# Power.net
KiCad netlist of a schematic drawn in Altium Designer
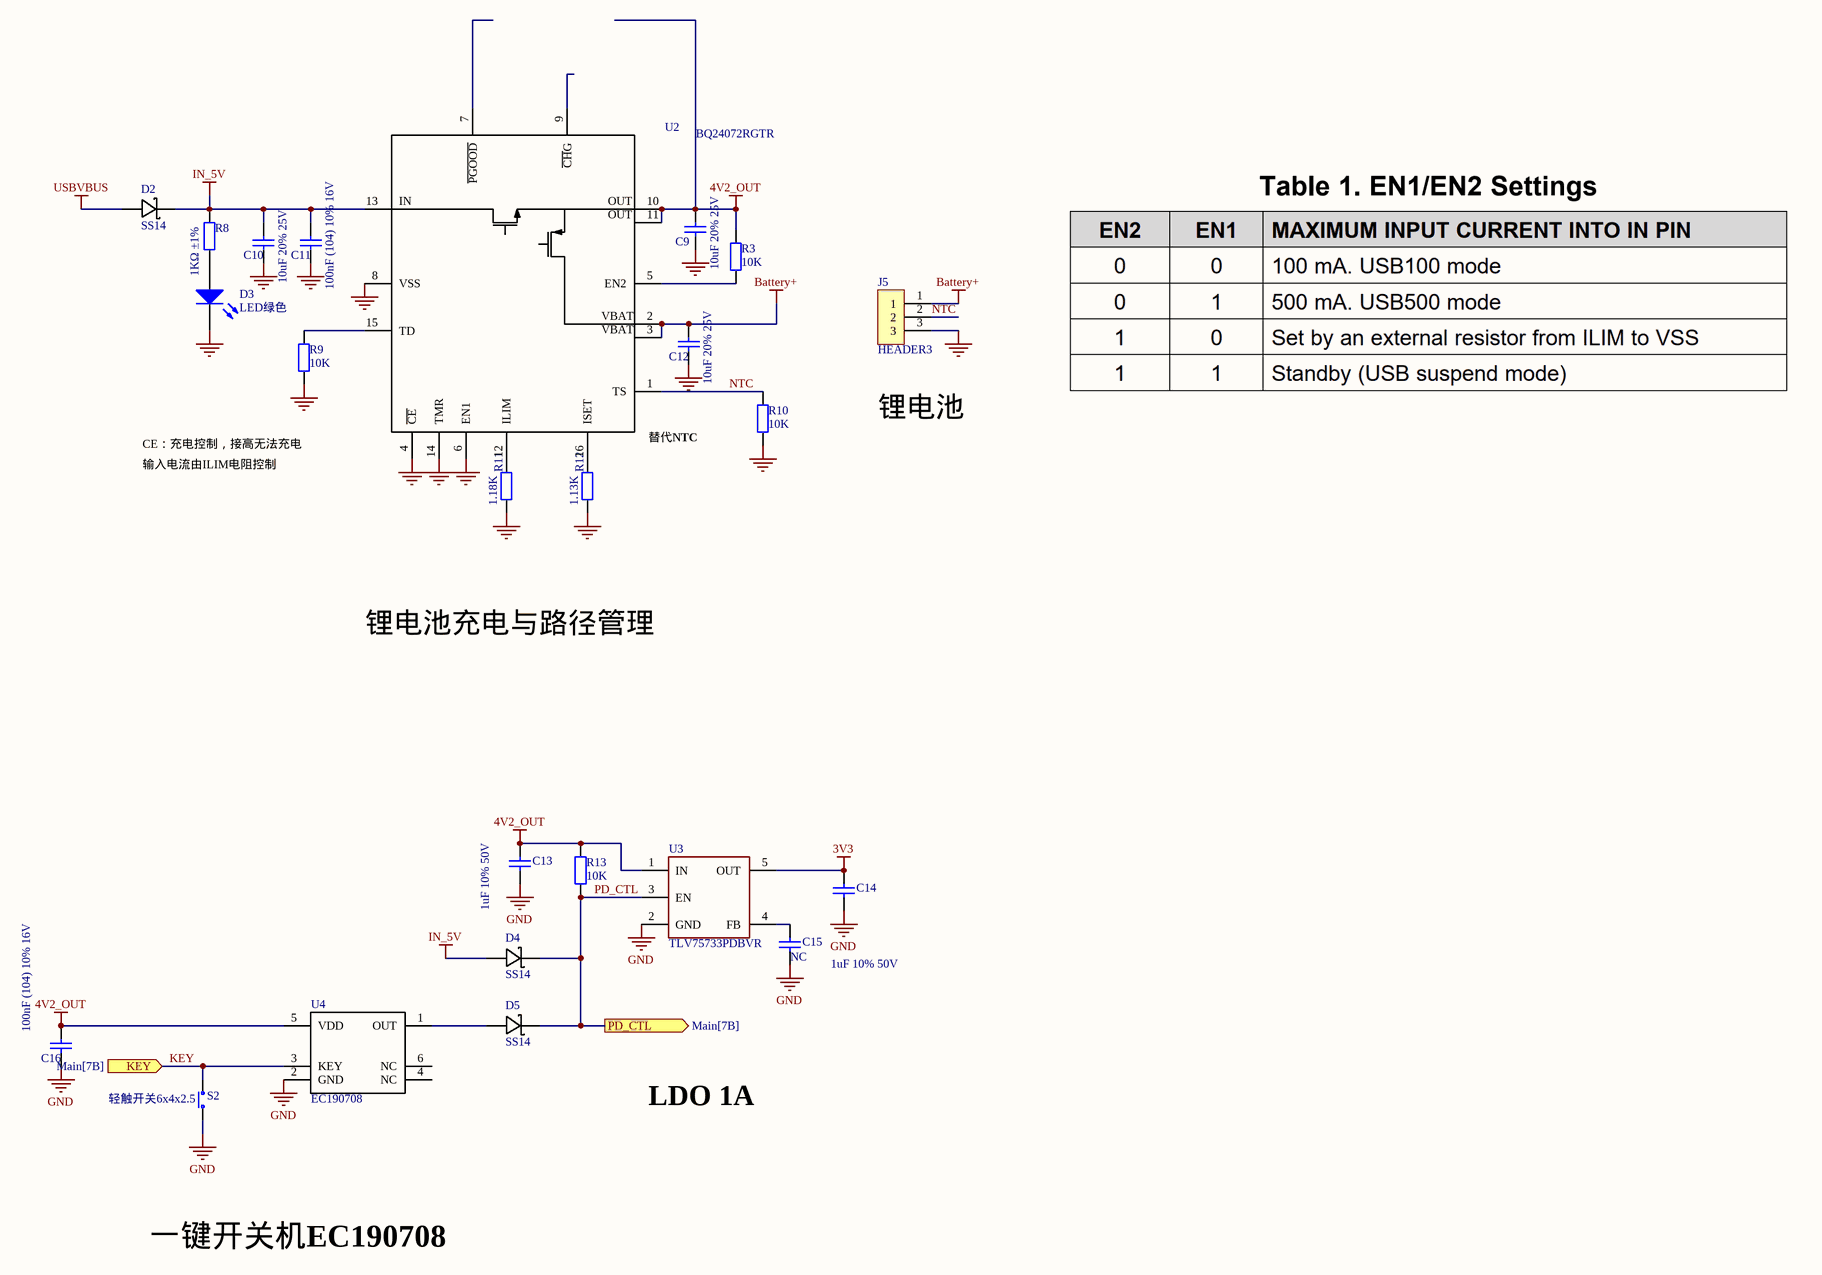
[diagram p0: Power.SchDoc]

(export (version "E")
  (design (tool "Eeschema 10.0.6"))
  (components
    (comp (ref "C9")
      (value "10uF 20% 25V")
      (footprint "0603_C")
      (description "贴片电容")
      (libsource (lib "Miscellaneous Devices LC") (part "0402 10uF (106) 20% 6.3V"))
    )
    (comp (ref "C10")
      (value "10uF 20% 25V")
      (footprint "0402_C")
      (description "贴片电容")
      (libsource (lib "Miscellaneous Devices LC") (part "0402 10uF (106) 20% 6.3V"))
    )
    (comp (ref "C11")
      (value "100nF (104) 10% 16V")
      (footprint "0402_C")
      (description "贴片电容")
      (libsource (lib "Miscellaneous Devices LC") (part "0603 100nF (104) 10% 50V"))
    )
    (comp (ref "C12")
      (value "10uF 20% 25V")
      (footprint "0603_C")
      (description "贴片电容")
      (libsource (lib "Miscellaneous Devices LC") (part "0402 10uF (106) 20% 6.3V"))
    )
    (comp (ref "C13")
      (value "1uF 10% 50V")
      (footprint "0402_C")
      (description "贴片电容")
      (libsource (lib "Cap") (part "0603 1uF (105) 10% 50V"))
    )
    (comp (ref "C14")
      (value "1uF 10% 50V")
      (footprint "0402_C")
      (description "贴片电容")
      (libsource (lib "Cap") (part "0603 1uF (105) 10% 50V"))
    )
    (comp (ref "C15")
      (value "NC")
      (footprint "0402_C")
      (description "贴片电容")
      (libsource (lib "Miscellaneous Devices LC") (part "0603 100nF (104) 10% 50V"))
    )
    (comp (ref "C16")
      (value "100nF (104) 10% 16V")
      (footprint "0402_C")
      (description "贴片电容")
      (libsource (lib "Miscellaneous Devices LC") (part "0603 100nF (104) 10% 50V"))
    )
    (comp (ref "D2")
      (value "SS14")
      (footprint "DO-214AC")
      (description "1A，40V")
      (libsource (lib "RFID") (part "SS14"))
    )
    (comp (ref "D3")
      (value "LED绿色")
      (footprint "LED_0402")
      (description "Typical INFRARED GaAs LED")
      (libsource (lib "RFID") (part "LED0"))
    )
    (comp (ref "D4")
      (value "SS14")
      (footprint "DO-214AC")
      (description "1A，40V")
      (libsource (lib "RFID") (part "SS14"))
    )
    (comp (ref "D5")
      (value "SS14")
      (footprint "DO-214AC")
      (description "1A，40V")
      (libsource (lib "RFID") (part "SS14"))
    )
    (comp (ref "J5") (value "HEADER3") (footprint "HEADER3") (libsource (lib "RFID") (part "HEADER3")))
    (comp (ref "R3")
      (value "10K")
      (footprint "0402_R")
      (description "Resistor")
      (libsource (lib "Miscellaneous Devices") (part "Res2"))
    )
    (comp (ref "R8")
      (value "1KΩ ±1%")
      (footprint "0402_R")
      (description "Resistor")
      (libsource (lib "") (part "Res2_1"))
    )
    (comp (ref "R9")
      (value "10K")
      (footprint "0402_R")
      (description "Resistor")
      (libsource (lib "Miscellaneous Devices") (part "Res2"))
    )
    (comp (ref "R10")
      (value "10K")
      (footprint "0402_R")
      (description "Resistor")
      (libsource (lib "Miscellaneous Devices") (part "Res2"))
    )
    (comp (ref "R11")
      (value "1.18K")
      (footprint "0402_R")
      (description "Resistor")
      (libsource (lib "Miscellaneous Devices") (part "Res2"))
    )
    (comp (ref "R12")
      (value "1.13K")
      (footprint "0402_R")
      (description "Resistor")
      (libsource (lib "Miscellaneous Devices") (part "Res2"))
    )
    (comp (ref "R13")
      (value "10K")
      (footprint "0402_R")
      (description "Resistor")
      (libsource (lib "") (part "Res2_1"))
    )
    (comp (ref "S2")
      (value "轻触开关6x4x2.5")
      (footprint "SW-SMD_L6.0-W4.0-LS7.2")
      (libsource (lib "RFID") (part "SW-PB_包脚U型小乌龟"))
    )
    (comp (ref "U2")
      (value "BQ24072RGTR")
      (footprint "QFN-16_L3.0-W3.0-P0.50-TL-EP")
      (description "TI")
      (libsource (lib "RFID") (part "BQ24072"))
    )
    (comp (ref "U3")
      (value "TLV75733PDBVR")
      (footprint "SOT-23_5")
      (libsource (lib "RFID") (part "TLV75733"))
    )
    (comp (ref "U4") (value "EC190708") (footprint "SOT-23-6") (libsource (lib "RFID") (part "EC190708")))
  )
  (nets
    (net (code "1") (name "/KEY") (class "Default")
      (node (ref "S2") (pin "1") (pinfunction "1_1") (pintype "passive"))
      (node (ref "U4") (pin "3") (pinfunction "KEY_3") (pintype "passive"))
    )
    (net (code "2") (name "/NTC") (class "Default")
      (node (ref "J5") (pin "2") (pinfunction "2_2") (pintype "power_in"))
      (node (ref "R10") (pin "1") (pinfunction "1_1") (pintype "passive"))
      (node (ref "U2") (pin "1") (pinfunction "TS_1") (pintype "passive"))
    )
    (net (code "3") (name "/PD_CTL") (class "Default")
      (node (ref "D4") (pin "2") (pinfunction "A_2") (pintype "passive"))
      (node (ref "D5") (pin "2") (pinfunction "A_2") (pintype "passive"))
      (node (ref "R13") (pin "1") (pinfunction "1_1") (pintype "passive"))
      (node (ref "U3") (pin "3") (pinfunction "EN_3") (pintype "passive"))
    )
    (net (code "4") (name "3V3") (class "Default")
      (node (ref "C14") (pin "2") (pinfunction "2_2") (pintype "passive"))
      (node (ref "U3") (pin "5") (pinfunction "OUT_5") (pintype "passive"))
    )
    (net (code "5") (name "4V2_OUT") (class "Default")
      (node (ref "C13") (pin "2") (pinfunction "2_2") (pintype "passive"))
      (node (ref "C16") (pin "2") (pinfunction "2_2") (pintype "passive"))
      (node (ref "C9") (pin "2") (pinfunction "2_2") (pintype "passive"))
      (node (ref "R13") (pin "2") (pinfunction "2_2") (pintype "passive"))
      (node (ref "R3") (pin "1") (pinfunction "1_1") (pintype "passive"))
      (node (ref "U2") (pin "10") (pinfunction "OUT_10") (pintype "passive"))
      (node (ref "U2") (pin "11") (pinfunction "OUT_11") (pintype "passive"))
      (node (ref "U3") (pin "1") (pinfunction "IN_1") (pintype "passive"))
      (node (ref "U4") (pin "5") (pinfunction "VDD_5") (pintype "passive"))
    )
    (net (code "6") (name "Battery+") (class "Default")
      (node (ref "C12") (pin "2") (pinfunction "2_2") (pintype "passive"))
      (node (ref "J5") (pin "1") (pinfunction "1_1") (pintype "power_in"))
      (node (ref "U2") (pin "2") (pinfunction "BAT_2") (pintype "passive"))
      (node (ref "U2") (pin "3") (pinfunction "BAT_3") (pintype "passive"))
    )
    (net (code "7") (name "GND") (class "Default")
      (node (ref "C10") (pin "1") (pinfunction "1_1") (pintype "passive"))
      (node (ref "C11") (pin "1") (pinfunction "1_1") (pintype "passive"))
      (node (ref "C12") (pin "1") (pinfunction "1_1") (pintype "passive"))
      (node (ref "C13") (pin "1") (pinfunction "1_1") (pintype "passive"))
      (node (ref "C14") (pin "1") (pinfunction "1_1") (pintype "passive"))
      (node (ref "C15") (pin "1") (pinfunction "1_1") (pintype "passive"))
      (node (ref "C16") (pin "1") (pinfunction "1_1") (pintype "passive"))
      (node (ref "C9") (pin "1") (pinfunction "1_1") (pintype "passive"))
      (node (ref "D3") (pin "K") (pinfunction "K_K") (pintype "passive"))
      (node (ref "J5") (pin "3") (pinfunction "3_3") (pintype "power_in"))
      (node (ref "R10") (pin "2") (pinfunction "2_2") (pintype "passive"))
      (node (ref "R11") (pin "2") (pinfunction "2_2") (pintype "passive"))
      (node (ref "R12") (pin "2") (pinfunction "2_2") (pintype "passive"))
      (node (ref "R9") (pin "2") (pinfunction "2_2") (pintype "passive"))
      (node (ref "S2") (pin "2") (pinfunction "2_2") (pintype "passive"))
      (node (ref "U2") (pin "14") (pinfunction "TMR_14") (pintype "passive"))
      (node (ref "U2") (pin "4") (pinfunction "~{CE}_4") (pintype "passive"))
      (node (ref "U2") (pin "6") (pinfunction "EN1_6") (pintype "passive"))
      (node (ref "U2") (pin "8") (pinfunction "VSS_8") (pintype "passive"))
      (node (ref "U3") (pin "2") (pinfunction "GND_2") (pintype "passive"))
      (node (ref "U4") (pin "2") (pinfunction "GND_2") (pintype "passive"))
    )
    (net (code "8") (name "IN_5V") (class "Default")
      (node (ref "C10") (pin "2") (pinfunction "2_2") (pintype "passive"))
      (node (ref "C11") (pin "2") (pinfunction "2_2") (pintype "passive"))
      (node (ref "D2") (pin "2") (pinfunction "A_2") (pintype "passive"))
      (node (ref "D4") (pin "1") (pinfunction "K_1") (pintype "passive"))
      (node (ref "R8") (pin "2") (pinfunction "2_2") (pintype "passive"))
      (node (ref "U2") (pin "13") (pinfunction "IN_13") (pintype "power_in"))
    )
    (net (code "9") (name "Net-(D3-PadA)") (class "Default")
      (node (ref "D3") (pin "A") (pinfunction "A_A") (pintype "passive"))
      (node (ref "R8") (pin "1") (pinfunction "1_1") (pintype "passive"))
    )
    (net (code "10") (name "Net-(D5-K)") (class "Default")
      (node (ref "D5") (pin "1") (pinfunction "K_1") (pintype "passive"))
      (node (ref "U4") (pin "1") (pinfunction "OUT_1") (pintype "passive"))
    )
    (net (code "11") (name "Net-(U2-EN2)") (class "Default")
      (node (ref "R3") (pin "2") (pinfunction "2_2") (pintype "passive"))
      (node (ref "U2") (pin "5") (pinfunction "EN2_5") (pintype "passive"))
    )
    (net (code "12") (name "Net-(U2-ILIM)") (class "Default")
      (node (ref "R11") (pin "1") (pinfunction "1_1") (pintype "passive"))
      (node (ref "U2") (pin "12") (pinfunction "ILIM_12") (pintype "passive"))
    )
    (net (code "13") (name "Net-(U2-ISET)") (class "Default")
      (node (ref "R12") (pin "1") (pinfunction "1_1") (pintype "passive"))
      (node (ref "U2") (pin "16") (pinfunction "ISET_16") (pintype "passive"))
    )
    (net (code "14") (name "Net-(U2-TD)") (class "Default")
      (node (ref "R9") (pin "1") (pinfunction "1_1") (pintype "passive"))
      (node (ref "U2") (pin "15") (pinfunction "TD_15") (pintype "passive"))
    )
    (net (code "15") (name "Net-(U3-FB)") (class "Default")
      (node (ref "C15") (pin "2") (pinfunction "2_2") (pintype "passive"))
      (node (ref "U3") (pin "4") (pinfunction "FB_4") (pintype "passive"))
    )
    (net (code "16") (name "USBVBUS") (class "Default")
      (node (ref "D2") (pin "1") (pinfunction "K_1") (pintype "passive"))
    )
    (net (code "17") (name "unconnected-(U2-~{CH}G-Pad9)") (class "Default")
      (node (ref "U2") (pin "9") (pinfunction "~{CH}G_9") (pintype "passive"))
    )
    (net (code "18") (name "unconnected-(U2-~{PGOOD}-Pad7)") (class "Default")
      (node (ref "U2") (pin "7") (pinfunction "~{PGOOD}_7") (pintype "passive"))
    )
    (net (code "19") (name "unconnected-(U4-NC-Pad4)") (class "Default")
      (node (ref "U4") (pin "4") (pinfunction "NC_4") (pintype "passive"))
    )
    (net (code "20") (name "unconnected-(U4-NC-Pad6)") (class "Default")
      (node (ref "U4") (pin "6") (pinfunction "NC_6") (pintype "passive"))
    )
  )
)
